# Comms.net
KiCad netlist of a schematic drawn in Altium Designer
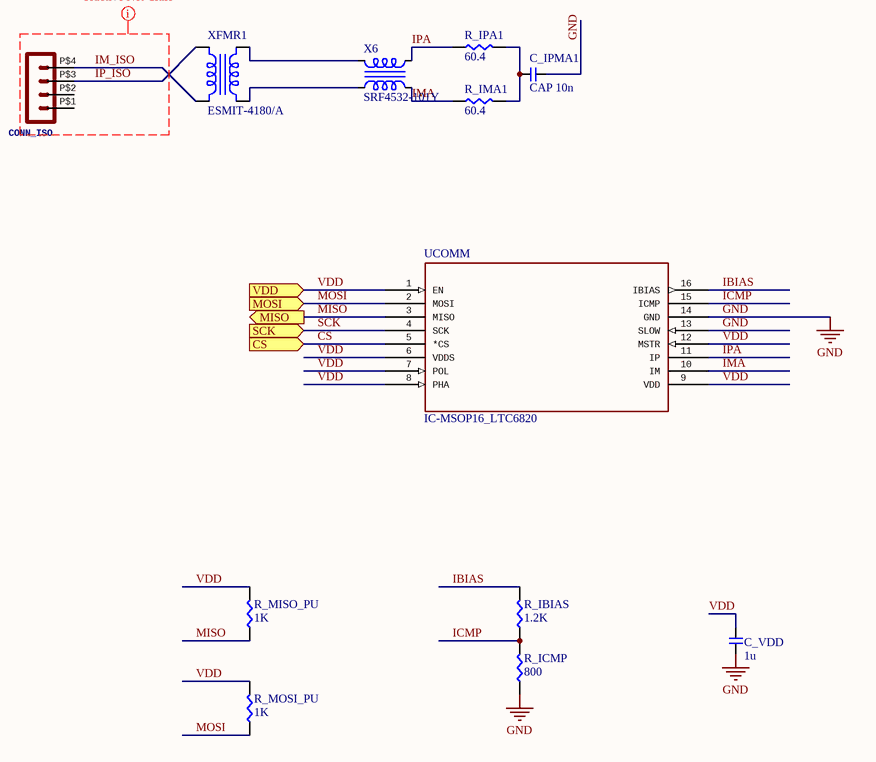
[diagram p0: Comms.SchDoc]

(export (version "E")
  (design (tool "Eeschema 10.0.6"))
  (components
    (comp (ref "CONN_ISO")
      (value "Molex - Micro-Fit 3.0 Series connector,  3.00mm (0.118\") pitch header, 4 positions.")
      (footprint "43650-0424")
      (libsource (lib "ife19_Elec_Conn_Library") (part "POS4_MF43650-0424"))
    )
    (comp (ref "C_IPMA1")
      (value "CAP 10n")
      (footprint "CAP-0603")
      (description "CAP-0603")
      (libsource (lib "ife18_TS_BMS_LTC6813_v2_Library") (part "CAP-0603"))
    )
    (comp (ref "C_VDD")
      (value "1u")
      (footprint "CAP-0603")
      (libsource (lib "altium-import") (part "root_1_CAP-0603_"))
    )
    (comp (ref "R_IBIAS")
      (value "1.2K")
      (footprint "RES-0603")
      (libsource (lib "altium-import") (part "root_1_RES-0603_"))
    )
    (comp (ref "R_ICMP")
      (value "800")
      (footprint "RES-0603")
      (libsource (lib "altium-import") (part "root_1_RES-0603_"))
    )
    (comp (ref "R_IMA1")
      (value "60.4")
      (footprint "RES-0603")
      (libsource (lib "ife18_TS_BMS_LTC6813_v2_Library") (part "RES-0603"))
    )
    (comp (ref "R_IPA1")
      (value "60.4")
      (footprint "RES-0603")
      (libsource (lib "ife18_TS_BMS_LTC6813_v2_Library") (part "RES-0603"))
    )
    (comp (ref "R_MISO_PU")
      (value "1K")
      (footprint "RES-0603")
      (libsource (lib "altium-import") (part "root_1_RES-0603_"))
    )
    (comp (ref "R_MOSI_PU")
      (value "1K")
      (footprint "RES-0603")
      (libsource (lib "altium-import") (part "root_1_RES-0603_"))
    )
    (comp (ref "UCOMM")
      (value "IC-MSOP16_LTC6820")
      (footprint "MSOP16")
      (libsource (lib "altium-import") (part "root_0_IC-MSOP16_LTC6820_"))
    )
    (comp (ref "X6")
      (value "SRF4532-101Y")
      (footprint "SRF4532")
      (libsource (lib "ife19_Elec_Library") (part "CMC_SRF4532"))
    )
    (comp (ref "XFMR1")
      (value "ESMIT-4180/A")
      (footprint "ISOXFMR_ESMIT4180")
      (libsource (lib "ife19_Elec_Library") (part "ISOXFMR_ESMIT4180"))
    )
  )
  (nets
    (net (code "1") (name "/CS") (class "Default")
      (node (ref "UCOMM") (pin "5") (pinfunction "*CS_5") (pintype "passive"))
    )
    (net (code "2") (name "/IBIAS") (class "Default")
      (node (ref "R_IBIAS") (pin "2") (pinfunction "2_2") (pintype "passive"))
      (node (ref "UCOMM") (pin "16") (pinfunction "IBIAS_16") (pintype "output"))
    )
    (net (code "3") (name "/ICMP") (class "Default")
      (node (ref "R_IBIAS") (pin "1") (pinfunction "1_1") (pintype "passive"))
      (node (ref "R_ICMP") (pin "2") (pinfunction "2_2") (pintype "passive"))
      (node (ref "UCOMM") (pin "15") (pinfunction "ICMP_15") (pintype "passive"))
    )
    (net (code "4") (name "/IMA") (class "Default")
      (node (ref "R_IMA1") (pin "2") (pinfunction "2_2") (pintype "passive"))
      (node (ref "UCOMM") (pin "10") (pinfunction "IM_10") (pintype "passive"))
      (node (ref "X6") (pin "1") (pinfunction "1_1") (pintype "passive"))
    )
    (net (code "5") (name "/IM_ISO") (class "Default")
      (node (ref "CONN_ISO") (pin "P$4") (pinfunction "4_P$4") (pintype "passive"))
      (node (ref "XFMR1") (pin "1") (pinfunction "1_1") (pintype "passive"))
    )
    (net (code "6") (name "/IPA") (class "Default")
      (node (ref "R_IPA1") (pin "2") (pinfunction "2_2") (pintype "passive"))
      (node (ref "UCOMM") (pin "11") (pinfunction "IP_11") (pintype "passive"))
      (node (ref "X6") (pin "4") (pinfunction "4_4") (pintype "passive"))
    )
    (net (code "7") (name "/IP_ISO") (class "Default")
      (node (ref "CONN_ISO") (pin "P$3") (pinfunction "3_P$3") (pintype "passive"))
      (node (ref "XFMR1") (pin "2") (pinfunction "2_2") (pintype "passive"))
    )
    (net (code "8") (name "/MISO") (class "Default")
      (node (ref "R_MISO_PU") (pin "1") (pinfunction "1_1") (pintype "passive"))
      (node (ref "UCOMM") (pin "3") (pinfunction "MISO_3") (pintype "passive"))
    )
    (net (code "9") (name "/MOSI") (class "Default")
      (node (ref "R_MOSI_PU") (pin "1") (pinfunction "1_1") (pintype "passive"))
      (node (ref "UCOMM") (pin "2") (pinfunction "MOSI_2") (pintype "passive"))
    )
    (net (code "10") (name "/SCK") (class "Default")
      (node (ref "UCOMM") (pin "4") (pinfunction "SCK_4") (pintype "passive"))
    )
    (net (code "11") (name "/VDD") (class "Default")
      (node (ref "C_VDD") (pin "2") (pinfunction "2_2") (pintype "passive"))
      (node (ref "R_MISO_PU") (pin "2") (pinfunction "2_2") (pintype "passive"))
      (node (ref "R_MOSI_PU") (pin "2") (pinfunction "2_2") (pintype "passive"))
      (node (ref "UCOMM") (pin "1") (pinfunction "EN_1") (pintype "input"))
      (node (ref "UCOMM") (pin "12") (pinfunction "MSTR_12") (pintype "input"))
      (node (ref "UCOMM") (pin "6") (pinfunction "VDDS_6") (pintype "power_in"))
      (node (ref "UCOMM") (pin "7") (pinfunction "POL_7") (pintype "input"))
      (node (ref "UCOMM") (pin "8") (pinfunction "PHA_8") (pintype "input"))
      (node (ref "UCOMM") (pin "9") (pinfunction "VDD_9") (pintype "power_in"))
    )
    (net (code "12") (name "GND") (class "Default")
      (node (ref "C_IPMA1") (pin "1") (pinfunction "1_1") (pintype "passive"))
      (node (ref "C_VDD") (pin "1") (pinfunction "1_1") (pintype "passive"))
      (node (ref "R_ICMP") (pin "1") (pinfunction "1_1") (pintype "passive"))
      (node (ref "UCOMM") (pin "13") (pinfunction "SLOW_13") (pintype "input"))
      (node (ref "UCOMM") (pin "14") (pinfunction "GND_14") (pintype "power_in"))
    )
    (net (code "13") (name "Net-(C_IPMA1-Pad2)") (class "Default")
      (node (ref "C_IPMA1") (pin "2") (pinfunction "2_2") (pintype "passive"))
      (node (ref "R_IMA1") (pin "1") (pinfunction "1_1") (pintype "passive"))
      (node (ref "R_IPA1") (pin "1") (pinfunction "1_1") (pintype "passive"))
    )
    (net (code "14") (name "Net-(X6-Pad2)") (class "Default")
      (node (ref "X6") (pin "2") (pinfunction "2_2") (pintype "passive"))
      (node (ref "XFMR1") (pin "4") (pinfunction "4_4") (pintype "passive"))
    )
    (net (code "15") (name "Net-(X6-Pad3)") (class "Default")
      (node (ref "X6") (pin "3") (pinfunction "3_3") (pintype "passive"))
      (node (ref "XFMR1") (pin "3") (pinfunction "3_3") (pintype "passive"))
    )
    (net (code "16") (name "unconnected-(CONN_ISO-1-PadP$1)") (class "Default")
      (node (ref "CONN_ISO") (pin "P$1") (pinfunction "1_P$1") (pintype "passive"))
    )
    (net (code "17") (name "unconnected-(CONN_ISO-2-PadP$2)") (class "Default")
      (node (ref "CONN_ISO") (pin "P$2") (pinfunction "2_P$2") (pintype "passive"))
    )
  )
)
